# LED_1_1.net
KiCad netlist of a schematic drawn in EAGLE
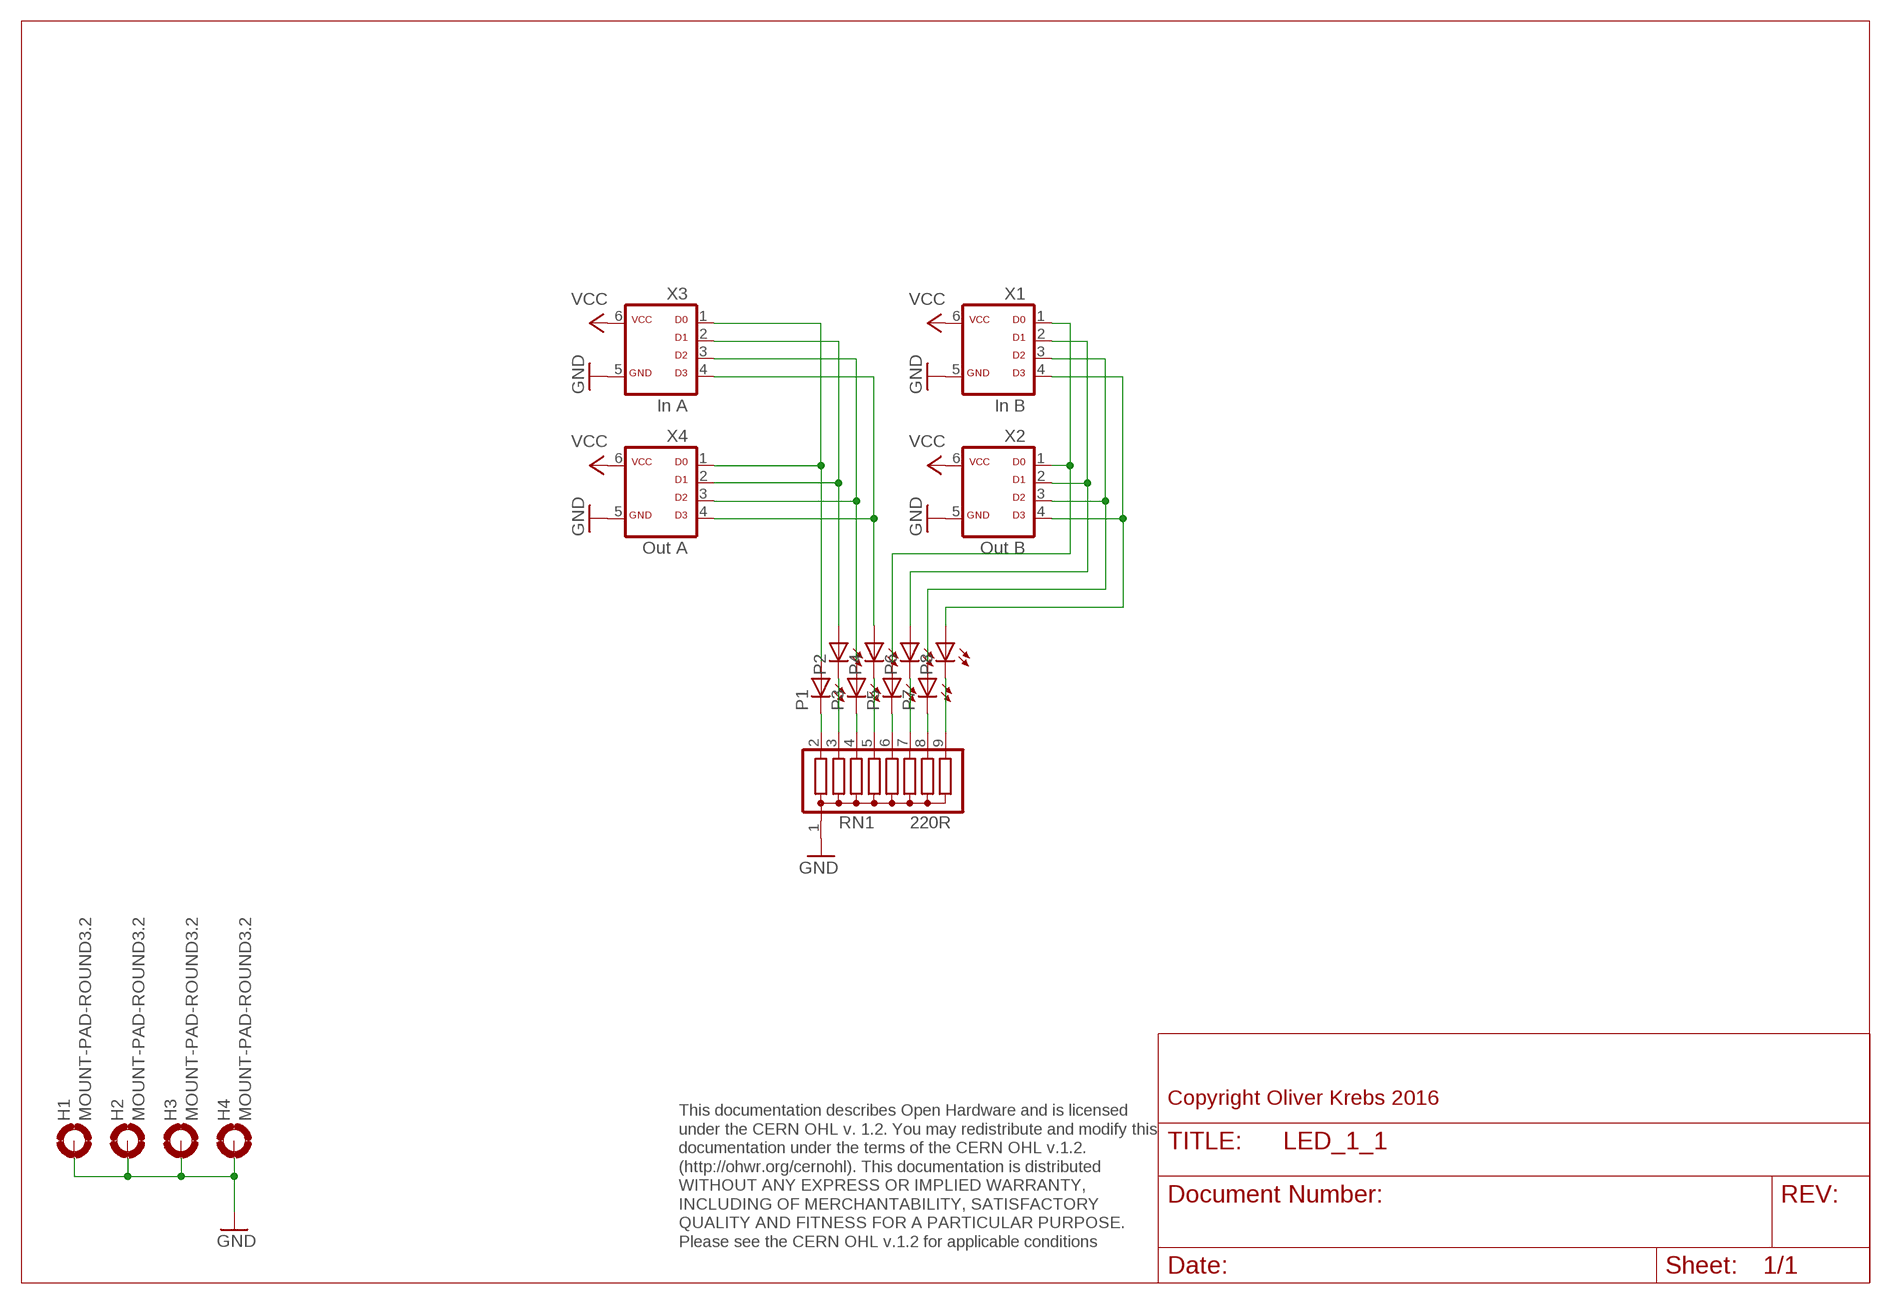
[diagram p0: schematic, sheet 1]

(export (version "E")
  (design (tool "Eeschema 10.0.6"))
  (components
    (comp (ref "H1")
      (value "MOUNT-PAD-ROUND3.2")
      (footprint "eagle-import:3,2-PAD")
      (libsource (lib "eagle-import") (part "MOUNT-PAD-ROUND3.2"))
    )
    (comp (ref "H2")
      (value "MOUNT-PAD-ROUND3.2")
      (footprint "eagle-import:3,2-PAD")
      (libsource (lib "eagle-import") (part "MOUNT-PAD-ROUND3.2"))
    )
    (comp (ref "H3")
      (value "MOUNT-PAD-ROUND3.2")
      (footprint "eagle-import:3,2-PAD")
      (libsource (lib "eagle-import") (part "MOUNT-PAD-ROUND3.2"))
    )
    (comp (ref "H4")
      (value "MOUNT-PAD-ROUND3.2")
      (footprint "eagle-import:3,2-PAD")
      (libsource (lib "eagle-import") (part "MOUNT-PAD-ROUND3.2"))
    )
    (comp (ref "P1")
      (value "LED3MM")
      (footprint "eagle-import:LED3MM")
      (libsource (lib "eagle-import") (part "LED3MM"))
    )
    (comp (ref "P2")
      (value "LED3MM")
      (footprint "eagle-import:LED3MM")
      (libsource (lib "eagle-import") (part "LED3MM"))
    )
    (comp (ref "P3")
      (value "LED3MM")
      (footprint "eagle-import:LED3MM")
      (libsource (lib "eagle-import") (part "LED3MM"))
    )
    (comp (ref "P4")
      (value "LED3MM")
      (footprint "eagle-import:LED3MM")
      (libsource (lib "eagle-import") (part "LED3MM"))
    )
    (comp (ref "P5")
      (value "LED3MM")
      (footprint "eagle-import:LED3MM")
      (libsource (lib "eagle-import") (part "LED3MM"))
    )
    (comp (ref "P6")
      (value "LED3MM")
      (footprint "eagle-import:LED3MM")
      (libsource (lib "eagle-import") (part "LED3MM"))
    )
    (comp (ref "P7")
      (value "LED3MM")
      (footprint "eagle-import:LED3MM")
      (libsource (lib "eagle-import") (part "LED3MM"))
    )
    (comp (ref "P8")
      (value "LED3MM")
      (footprint "eagle-import:LED3MM")
      (libsource (lib "eagle-import") (part "LED3MM"))
    )
    (comp (ref "RN1")
      (value "220R")
      (footprint "eagle-import:SIL9")
      (libsource (lib "eagle-import") (part "G08R"))
    )
    (comp (ref "X1")
      (value "In B")
      (footprint "eagle-import:ML-6")
      (libsource (lib "eagle-import") (part "ML6D"))
    )
    (comp (ref "X2")
      (value "Out B")
      (footprint "eagle-import:ML-6")
      (libsource (lib "eagle-import") (part "ML6D"))
    )
    (comp (ref "X3")
      (value "In A")
      (footprint "eagle-import:ML-6")
      (libsource (lib "eagle-import") (part "ML6D"))
    )
    (comp (ref "X4")
      (value "Out A")
      (footprint "eagle-import:ML-6")
      (libsource (lib "eagle-import") (part "ML6D"))
    )
  )
  (nets
    (net (code "1") (name "GND") (class "Default")
      (node (ref "H1") (pin "B3,2") (pinfunction "MOUNT_B3,2") (pintype "passive"))
      (node (ref "H2") (pin "B3,2") (pinfunction "MOUNT_B3,2") (pintype "passive"))
      (node (ref "H3") (pin "B3,2") (pinfunction "MOUNT_B3,2") (pintype "passive"))
      (node (ref "H4") (pin "B3,2") (pinfunction "MOUNT_B3,2") (pintype "passive"))
      (node (ref "RN1") (pin "1") (pinfunction "1_1") (pintype "passive"))
      (node (ref "X1") (pin "5") (pinfunction "5_5") (pintype "passive"))
      (node (ref "X2") (pin "5") (pinfunction "5_5") (pintype "passive"))
      (node (ref "X3") (pin "5") (pinfunction "5_5") (pintype "passive"))
      (node (ref "X4") (pin "5") (pinfunction "5_5") (pintype "passive"))
    )
    (net (code "2") (name "Net-(P1-C)") (class "Default")
      (node (ref "P1") (pin "K") (pinfunction "C_K") (pintype "passive"))
      (node (ref "RN1") (pin "2") (pinfunction "2_2") (pintype "passive"))
    )
    (net (code "3") (name "Net-(P1-PadA)") (class "Default")
      (node (ref "P1") (pin "A") (pinfunction "A_A") (pintype "passive"))
      (node (ref "X3") (pin "1") (pinfunction "1_1") (pintype "passive"))
      (node (ref "X4") (pin "1") (pinfunction "1_1") (pintype "passive"))
    )
    (net (code "4") (name "Net-(P2-C)") (class "Default")
      (node (ref "P2") (pin "K") (pinfunction "C_K") (pintype "passive"))
      (node (ref "RN1") (pin "3") (pinfunction "3_3") (pintype "passive"))
    )
    (net (code "5") (name "Net-(P2-PadA)") (class "Default")
      (node (ref "P2") (pin "A") (pinfunction "A_A") (pintype "passive"))
      (node (ref "X3") (pin "2") (pinfunction "2_2") (pintype "passive"))
      (node (ref "X4") (pin "2") (pinfunction "2_2") (pintype "passive"))
    )
    (net (code "6") (name "Net-(P3-C)") (class "Default")
      (node (ref "P3") (pin "K") (pinfunction "C_K") (pintype "passive"))
      (node (ref "RN1") (pin "4") (pinfunction "4_4") (pintype "passive"))
    )
    (net (code "7") (name "Net-(P3-PadA)") (class "Default")
      (node (ref "P3") (pin "A") (pinfunction "A_A") (pintype "passive"))
      (node (ref "X3") (pin "3") (pinfunction "3_3") (pintype "passive"))
      (node (ref "X4") (pin "3") (pinfunction "3_3") (pintype "passive"))
    )
    (net (code "8") (name "Net-(P4-C)") (class "Default")
      (node (ref "P4") (pin "K") (pinfunction "C_K") (pintype "passive"))
      (node (ref "RN1") (pin "5") (pinfunction "5_5") (pintype "passive"))
    )
    (net (code "9") (name "Net-(P4-PadA)") (class "Default")
      (node (ref "P4") (pin "A") (pinfunction "A_A") (pintype "passive"))
      (node (ref "X3") (pin "4") (pinfunction "4_4") (pintype "passive"))
      (node (ref "X4") (pin "4") (pinfunction "4_4") (pintype "passive"))
    )
    (net (code "10") (name "Net-(P5-C)") (class "Default")
      (node (ref "P5") (pin "K") (pinfunction "C_K") (pintype "passive"))
      (node (ref "RN1") (pin "6") (pinfunction "6_6") (pintype "passive"))
    )
    (net (code "11") (name "Net-(P5-PadA)") (class "Default")
      (node (ref "P5") (pin "A") (pinfunction "A_A") (pintype "passive"))
      (node (ref "X1") (pin "1") (pinfunction "1_1") (pintype "passive"))
      (node (ref "X2") (pin "1") (pinfunction "1_1") (pintype "passive"))
    )
    (net (code "12") (name "Net-(P6-C)") (class "Default")
      (node (ref "P6") (pin "K") (pinfunction "C_K") (pintype "passive"))
      (node (ref "RN1") (pin "7") (pinfunction "7_7") (pintype "passive"))
    )
    (net (code "13") (name "Net-(P6-PadA)") (class "Default")
      (node (ref "P6") (pin "A") (pinfunction "A_A") (pintype "passive"))
      (node (ref "X1") (pin "2") (pinfunction "2_2") (pintype "passive"))
      (node (ref "X2") (pin "2") (pinfunction "2_2") (pintype "passive"))
    )
    (net (code "14") (name "Net-(P7-C)") (class "Default")
      (node (ref "P7") (pin "K") (pinfunction "C_K") (pintype "passive"))
      (node (ref "RN1") (pin "8") (pinfunction "8_8") (pintype "passive"))
    )
    (net (code "15") (name "Net-(P7-PadA)") (class "Default")
      (node (ref "P7") (pin "A") (pinfunction "A_A") (pintype "passive"))
      (node (ref "X1") (pin "3") (pinfunction "3_3") (pintype "passive"))
      (node (ref "X2") (pin "3") (pinfunction "3_3") (pintype "passive"))
    )
    (net (code "16") (name "Net-(P8-C)") (class "Default")
      (node (ref "P8") (pin "K") (pinfunction "C_K") (pintype "passive"))
      (node (ref "RN1") (pin "9") (pinfunction "9_9") (pintype "passive"))
    )
    (net (code "17") (name "Net-(P8-PadA)") (class "Default")
      (node (ref "P8") (pin "A") (pinfunction "A_A") (pintype "passive"))
      (node (ref "X1") (pin "4") (pinfunction "4_4") (pintype "passive"))
      (node (ref "X2") (pin "4") (pinfunction "4_4") (pintype "passive"))
    )
    (net (code "18") (name "VCC") (class "Default")
      (node (ref "X1") (pin "6") (pinfunction "6_6") (pintype "passive"))
      (node (ref "X2") (pin "6") (pinfunction "6_6") (pintype "passive"))
      (node (ref "X3") (pin "6") (pinfunction "6_6") (pintype "passive"))
      (node (ref "X4") (pin "6") (pinfunction "6_6") (pintype "passive"))
    )
  )
)
